# design.net
KiCad netlist of a schematic drawn in Altium Designer
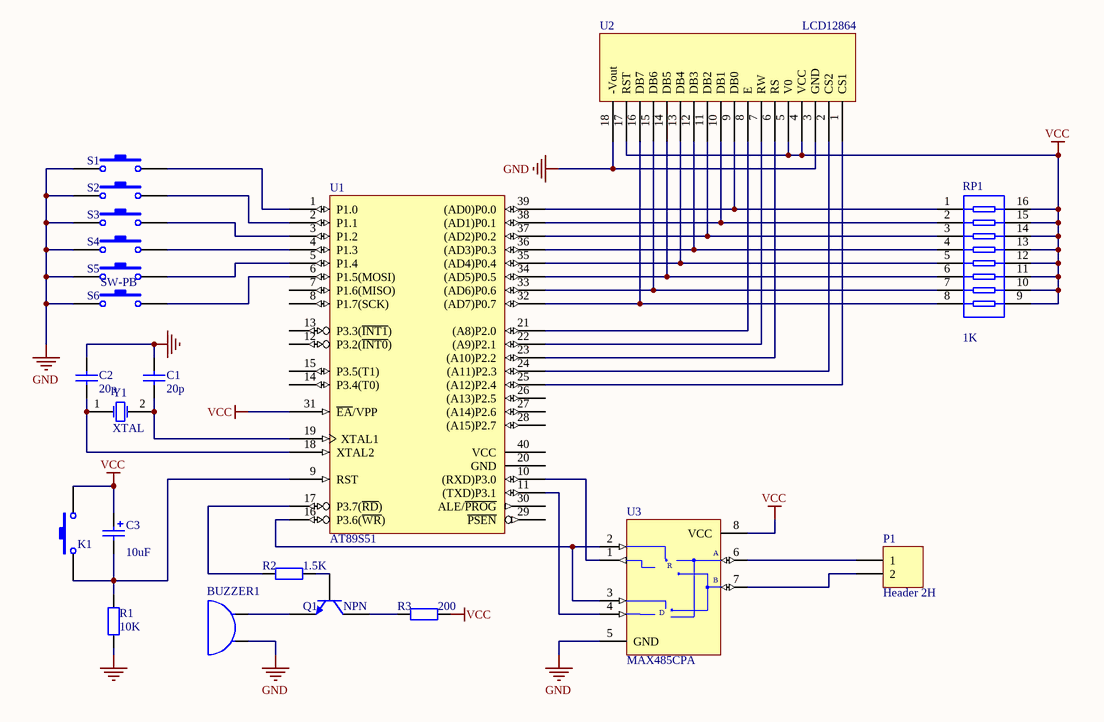
[diagram p0: 主机.SchDoc]

(export (version "E")
  (design (tool "Eeschema 10.0.6"))
  (components
    (comp (ref "BUZZER1") (value "BUZZER") (footprint "SP/10/14") (libsource (lib "原理图封装库") (part "BUZZER")))
    (comp (ref "C1")
      (value "20p")
      (footprint "RAD-0.3")
      (description "Capacitor")
      (fields (field (name "Comment") "Cap") (field (name "PUBLISHER") "Altium Limited"))
      (libsource (lib "Miscellaneous Devices") (part "Cap"))
    )
    (comp (ref "C2")
      (value "20p")
      (footprint "RAD-0.3")
      (description "Capacitor")
      (fields (field (name "Comment") "Cap") (field (name "PUBLISHER") "Altium Limited"))
      (libsource (lib "Miscellaneous Devices") (part "Cap"))
    )
    (comp (ref "C3")
      (value "10uF")
      (footprint "POLAR0.8")
      (description "Polarized Capacitor (Axial)")
      (fields (field (name "Comment") "Cap Pol2") (field (name "PUBLISHER") "Altium Limited"))
      (libsource (lib "Miscellaneous Devices") (part "Cap Pol2"))
    )
    (comp (ref "K1")
      (value "SW-PB")
      (footprint "SPST-2")
      (description "Switch")
      (fields (field (name "PUBLISHER") "Altium Limited"))
      (libsource (lib "Miscellaneous Devices") (part "SW-PB"))
    )
    (comp (ref "P1")
      (value "Header 2H")
      (footprint "HDR1X2H")
      (description "Header, 2-Pin, Right Angle")
      (fields (field (name "PUBLISHER") "Altium Limited"))
      (libsource (lib "Miscellaneous Connectors") (part "Header 2H"))
    )
    (comp (ref "Q1")
      (value "NPN")
      (footprint "TO-226")
      (description "NPN Bipolar Transistor")
      (fields (field (name "PUBLISHER") "Altium Limited"))
      (libsource (lib "Miscellaneous Devices") (part "NPN"))
    )
    (comp (ref "R1")
      (value "10K")
      (footprint "AXIAL-0.3")
      (description "Resistor")
      (fields (field (name "PUBLISHER") "Altium Limited"))
      (libsource (lib "Miscellaneous Devices") (part "Res2"))
    )
    (comp (ref "R2")
      (value "1.5K")
      (footprint "AXIAL-0.3")
      (description "Resistor")
      (fields (field (name "Comment") "10K") (field (name "PUBLISHER") "Altium Limited"))
      (libsource (lib "") (part "Res2_1"))
    )
    (comp (ref "R3")
      (value "200")
      (footprint "AXIAL-0.3")
      (description "Resistor")
      (fields (field (name "Comment") "10K") (field (name "PUBLISHER") "Altium Limited"))
      (libsource (lib "") (part "Res2_1"))
    )
    (comp (ref "RP1")
      (value "1K")
      (footprint "SSOP16")
      (description "Isolated Resistor Network")
      (fields (field (name "Comment") "Res Pack4") (field (name "PUBLISHER") "Altium Limited"))
      (libsource (lib "Miscellaneous Devices") (part "Res Pack4"))
    )
    (comp (ref "S1")
      (value "SW-PB")
      (footprint "SPST-2")
      (description "Switch")
      (fields (field (name "PUBLISHER") "Altium Limited"))
      (libsource (lib "Miscellaneous Devices") (part "SW-PB"))
    )
    (comp (ref "S2")
      (value "SW-PB")
      (footprint "SPST-2")
      (description "Switch")
      (fields (field (name "PUBLISHER") "Altium Limited"))
      (libsource (lib "Miscellaneous Devices") (part "SW-PB"))
    )
    (comp (ref "S3")
      (value "SW-PB")
      (footprint "SPST-2")
      (description "Switch")
      (fields (field (name "PUBLISHER") "Altium Limited"))
      (libsource (lib "Miscellaneous Devices") (part "SW-PB"))
    )
    (comp (ref "S4")
      (value "SW-PB")
      (footprint "SPST-2")
      (description "Switch")
      (fields (field (name "PUBLISHER") "Altium Limited"))
      (libsource (lib "Miscellaneous Devices") (part "SW-PB"))
    )
    (comp (ref "S5")
      (value "SW-PB")
      (footprint "SPST-2")
      (description "Switch")
      (fields (field (name "PUBLISHER") "Altium Limited"))
      (libsource (lib "Miscellaneous Devices") (part "SW-PB"))
    )
    (comp (ref "S6")
      (value "SW-PB")
      (footprint "SPST-2")
      (description "Switch")
      (fields (field (name "PUBLISHER") "Altium Limited"))
      (libsource (lib "Miscellaneous Devices") (part "SW-PB"))
    )
    (comp (ref "U1")
      (value "AT89S51")
      (footprint "DIP-40")
      (description "8-Bit Microcontroller with 4K ISP Flash ROM")
      (libsource (lib "Atmel Microcontroller 8051 Architecture") (part "AT89S51"))
    )
    (comp (ref "U2") (value "LCD12864") (footprint "SIL-20") (libsource (lib "LCD12864") (part "LCD12864")))
    (comp (ref "U3")
      (value "MAX485CPA")
      (footprint "PA8")
      (description "Low-Power, Slew-Rate-Limited RS-485/RS-422 Transceiver")
      (fields (field (name "PUBLISHER") "Altium Limited"))
      (libsource (lib "Maxim Communication Transceiver") (part "MAX485CPA"))
    )
    (comp (ref "Y1")
      (value "XTAL")
      (footprint "R38")
      (description "Crystal Oscillator")
      (fields (field (name "PUBLISHER") "Altium Limited"))
      (libsource (lib "Miscellaneous Devices") (part "XTAL"))
    )
  )
  (nets
    (net (code "1") (name "GND") (class "Default")
      (node (ref "BUZZER1") (pin "1") (pinfunction "1_1") (pintype "passive"))
      (node (ref "C1") (pin "1") (pinfunction "1_1") (pintype "passive"))
      (node (ref "C2") (pin "1") (pinfunction "1_1") (pintype "passive"))
      (node (ref "R1") (pin "2") (pinfunction "2_2") (pintype "passive"))
      (node (ref "S1") (pin "1") (pinfunction "1_1") (pintype "passive"))
      (node (ref "S2") (pin "1") (pinfunction "1_1") (pintype "passive"))
      (node (ref "S3") (pin "1") (pinfunction "1_1") (pintype "passive"))
      (node (ref "S4") (pin "1") (pinfunction "1_1") (pintype "passive"))
      (node (ref "S5") (pin "1") (pinfunction "1_1") (pintype "passive"))
      (node (ref "S6") (pin "1") (pinfunction "1_1") (pintype "passive"))
      (node (ref "U2") (pin "18") (pinfunction "-Vout_18") (pintype "passive"))
      (node (ref "U2") (pin "3") (pinfunction "GND_3") (pintype "passive"))
      (node (ref "U3") (pin "5") (pinfunction "GND_5") (pintype "power_in"))
    )
    (net (code "2") (name "Net-(Q1-B)") (class "Default")
      (node (ref "Q1") (pin "2") (pinfunction "B_2") (pintype "passive"))
      (node (ref "R2") (pin "2") (pinfunction "2_2") (pintype "passive"))
    )
    (net (code "3") (name "Net-(Q1-C)") (class "Default")
      (node (ref "Q1") (pin "1") (pinfunction "C_1") (pintype "passive"))
      (node (ref "R3") (pin "1") (pinfunction "1_1") (pintype "passive"))
    )
    (net (code "4") (name "Net-(Q1-E)") (class "Default")
      (node (ref "BUZZER1") (pin "2") (pinfunction "2_2") (pintype "passive"))
      (node (ref "Q1") (pin "3") (pinfunction "E_3") (pintype "passive"))
    )
    (net (code "5") (name "Net-(U1-(A8)P2.0)") (class "Default")
      (node (ref "U1") (pin "21") (pinfunction "(A8)P2.0_21") (pintype "bidirectional"))
      (node (ref "U2") (pin "8") (pinfunction "E_8") (pintype "passive"))
    )
    (net (code "6") (name "Net-(U1-(A9)P2.1)") (class "Default")
      (node (ref "U1") (pin "22") (pinfunction "(A9)P2.1_22") (pintype "bidirectional"))
      (node (ref "U2") (pin "7") (pinfunction "RW_7") (pintype "passive"))
    )
    (net (code "7") (name "Net-(U1-(A10)P2.2)") (class "Default")
      (node (ref "U1") (pin "23") (pinfunction "(A10)P2.2_23") (pintype "bidirectional"))
      (node (ref "U2") (pin "6") (pinfunction "RS_6") (pintype "passive"))
    )
    (net (code "8") (name "Net-(U1-(A11)P2.3)") (class "Default")
      (node (ref "U1") (pin "24") (pinfunction "(A11)P2.3_24") (pintype "bidirectional"))
      (node (ref "U2") (pin "2") (pinfunction "CS2_2") (pintype "passive"))
    )
    (net (code "9") (name "Net-(U1-(A12)P2.4)") (class "Default")
      (node (ref "U1") (pin "25") (pinfunction "(A12)P2.4_25") (pintype "bidirectional"))
      (node (ref "U2") (pin "1") (pinfunction "CS1_1") (pintype "passive"))
    )
    (net (code "10") (name "Net-(U1-(AD0)P0.0)") (class "Default")
      (node (ref "RP1") (pin "1") (pinfunction "1_1") (pintype "passive"))
      (node (ref "U1") (pin "39") (pinfunction "(AD0)P0.0_39") (pintype "bidirectional"))
      (node (ref "U2") (pin "9") (pinfunction "DB0_9") (pintype "passive"))
    )
    (net (code "11") (name "Net-(U1-(AD1)P0.1)") (class "Default")
      (node (ref "RP1") (pin "2") (pinfunction "2_2") (pintype "passive"))
      (node (ref "U1") (pin "38") (pinfunction "(AD1)P0.1_38") (pintype "bidirectional"))
      (node (ref "U2") (pin "10") (pinfunction "DB1_10") (pintype "passive"))
    )
    (net (code "12") (name "Net-(U1-(AD2)P0.2)") (class "Default")
      (node (ref "RP1") (pin "3") (pinfunction "3_3") (pintype "passive"))
      (node (ref "U1") (pin "37") (pinfunction "(AD2)P0.2_37") (pintype "bidirectional"))
      (node (ref "U2") (pin "11") (pinfunction "DB2_11") (pintype "passive"))
    )
    (net (code "13") (name "Net-(U1-(AD3)P0.3)") (class "Default")
      (node (ref "RP1") (pin "4") (pinfunction "4_4") (pintype "passive"))
      (node (ref "U1") (pin "36") (pinfunction "(AD3)P0.3_36") (pintype "bidirectional"))
      (node (ref "U2") (pin "12") (pinfunction "DB3_12") (pintype "passive"))
    )
    (net (code "14") (name "Net-(U1-(AD4)P0.4)") (class "Default")
      (node (ref "RP1") (pin "5") (pinfunction "5_5") (pintype "passive"))
      (node (ref "U1") (pin "35") (pinfunction "(AD4)P0.4_35") (pintype "bidirectional"))
      (node (ref "U2") (pin "13") (pinfunction "DB4_13") (pintype "passive"))
    )
    (net (code "15") (name "Net-(U1-(AD5)P0.5)") (class "Default")
      (node (ref "RP1") (pin "6") (pinfunction "6_6") (pintype "passive"))
      (node (ref "U1") (pin "34") (pinfunction "(AD5)P0.5_34") (pintype "bidirectional"))
      (node (ref "U2") (pin "14") (pinfunction "DB5_14") (pintype "passive"))
    )
    (net (code "16") (name "Net-(U1-(AD6)P0.6)") (class "Default")
      (node (ref "RP1") (pin "7") (pinfunction "7_7") (pintype "passive"))
      (node (ref "U1") (pin "33") (pinfunction "(AD6)P0.6_33") (pintype "bidirectional"))
      (node (ref "U2") (pin "15") (pinfunction "DB6_15") (pintype "passive"))
    )
    (net (code "17") (name "Net-(U1-(AD7)P0.7)") (class "Default")
      (node (ref "RP1") (pin "8") (pinfunction "8_8") (pintype "passive"))
      (node (ref "U1") (pin "32") (pinfunction "(AD7)P0.7_32") (pintype "bidirectional"))
      (node (ref "U2") (pin "16") (pinfunction "DB7_16") (pintype "passive"))
    )
    (net (code "18") (name "Net-(U1-(RXD)P3.0)") (class "Default")
      (node (ref "U1") (pin "10") (pinfunction "(RXD)P3.0_10") (pintype "bidirectional"))
      (node (ref "U3") (pin "1") (pinfunction "RO_1") (pintype "output"))
    )
    (net (code "19") (name "Net-(U1-(TXD)P3.1)") (class "Default")
      (node (ref "U1") (pin "11") (pinfunction "(TXD)P3.1_11") (pintype "bidirectional"))
      (node (ref "U3") (pin "4") (pinfunction "DI_4") (pintype "input"))
    )
    (net (code "20") (name "Net-(U1-P1.0)") (class "Default")
      (node (ref "S1") (pin "2") (pinfunction "2_2") (pintype "passive"))
      (node (ref "U1") (pin "1") (pinfunction "P1.0_1") (pintype "bidirectional"))
    )
    (net (code "21") (name "Net-(U1-P1.1)") (class "Default")
      (node (ref "S2") (pin "2") (pinfunction "2_2") (pintype "passive"))
      (node (ref "U1") (pin "2") (pinfunction "P1.1_2") (pintype "bidirectional"))
    )
    (net (code "22") (name "Net-(U1-P1.2)") (class "Default")
      (node (ref "S3") (pin "2") (pinfunction "2_2") (pintype "passive"))
      (node (ref "U1") (pin "3") (pinfunction "P1.2_3") (pintype "bidirectional"))
    )
    (net (code "23") (name "Net-(U1-P1.3)") (class "Default")
      (node (ref "S4") (pin "2") (pinfunction "2_2") (pintype "passive"))
      (node (ref "U1") (pin "4") (pinfunction "P1.3_4") (pintype "bidirectional"))
    )
    (net (code "24") (name "Net-(U1-P1.4)") (class "Default")
      (node (ref "S5") (pin "2") (pinfunction "2_2") (pintype "passive"))
      (node (ref "U1") (pin "5") (pinfunction "P1.4_5") (pintype "bidirectional"))
    )
    (net (code "25") (name "Net-(U1-P1.5(MOSI))") (class "Default")
      (node (ref "S6") (pin "2") (pinfunction "2_2") (pintype "passive"))
      (node (ref "U1") (pin "6") (pinfunction "P1.5(MOSI)_6") (pintype "bidirectional"))
    )
    (net (code "26") (name "Net-(U1-P3.6(~{WR}))") (class "Default")
      (node (ref "U1") (pin "16") (pinfunction "P3.6(~{WR})_16") (pintype "bidirectional"))
      (node (ref "U3") (pin "2") (pinfunction "~{RE}_2") (pintype "input"))
      (node (ref "U3") (pin "3") (pinfunction "DE_3") (pintype "input"))
    )
    (net (code "27") (name "Net-(U1-P3.7(~{RD}))") (class "Default")
      (node (ref "R2") (pin "1") (pinfunction "1_1") (pintype "passive"))
      (node (ref "U1") (pin "17") (pinfunction "P3.7(~{RD})_17") (pintype "bidirectional"))
    )
    (net (code "28") (name "Net-(U1-RST)") (class "Default")
      (node (ref "C3") (pin "2") (pinfunction "2_2") (pintype "passive"))
      (node (ref "K1") (pin "1") (pinfunction "1_1") (pintype "passive"))
      (node (ref "R1") (pin "1") (pinfunction "1_1") (pintype "passive"))
      (node (ref "U1") (pin "9") (pinfunction "RST_9") (pintype "input"))
    )
    (net (code "29") (name "Net-(U1-XTAL1)") (class "Default")
      (node (ref "C1") (pin "2") (pinfunction "2_2") (pintype "passive"))
      (node (ref "U1") (pin "19") (pinfunction "XTAL1_19") (pintype "input"))
      (node (ref "Y1") (pin "2") (pinfunction "OSC2_2") (pintype "passive"))
    )
    (net (code "30") (name "Net-(U1-XTAL2)") (class "Default")
      (node (ref "C2") (pin "2") (pinfunction "2_2") (pintype "passive"))
      (node (ref "U1") (pin "18") (pinfunction "XTAL2_18") (pintype "input"))
      (node (ref "Y1") (pin "1") (pinfunction "OSC1_1") (pintype "passive"))
    )
    (net (code "31") (name "Net-(U3-A)") (class "Default")
      (node (ref "P1") (pin "1") (pinfunction "1_1") (pintype "passive"))
      (node (ref "U3") (pin "6") (pinfunction "A_6") (pintype "bidirectional"))
    )
    (net (code "32") (name "Net-(U3-B)") (class "Default")
      (node (ref "P1") (pin "2") (pinfunction "2_2") (pintype "passive"))
      (node (ref "U3") (pin "7") (pinfunction "B_7") (pintype "bidirectional"))
    )
    (net (code "33") (name "VCC") (class "Default")
      (node (ref "C3") (pin "1") (pinfunction "1_1") (pintype "passive"))
      (node (ref "K1") (pin "2") (pinfunction "2_2") (pintype "passive"))
      (node (ref "R3") (pin "2") (pinfunction "2_2") (pintype "passive"))
      (node (ref "RP1") (pin "10") (pinfunction "10_10") (pintype "passive"))
      (node (ref "RP1") (pin "11") (pinfunction "11_11") (pintype "passive"))
      (node (ref "RP1") (pin "12") (pinfunction "12_12") (pintype "passive"))
      (node (ref "RP1") (pin "13") (pinfunction "13_13") (pintype "passive"))
      (node (ref "RP1") (pin "14") (pinfunction "14_14") (pintype "passive"))
      (node (ref "RP1") (pin "15") (pinfunction "15_15") (pintype "passive"))
      (node (ref "RP1") (pin "16") (pinfunction "16_16") (pintype "passive"))
      (node (ref "RP1") (pin "9") (pinfunction "9_9") (pintype "passive"))
      (node (ref "U1") (pin "31") (pinfunction "~{EA}/VPP_31") (pintype "input"))
      (node (ref "U2") (pin "17") (pinfunction "RST_17") (pintype "passive"))
      (node (ref "U2") (pin "4") (pinfunction "VCC_4") (pintype "passive"))
      (node (ref "U2") (pin "5") (pinfunction "V0_5") (pintype "passive"))
      (node (ref "U3") (pin "8") (pinfunction "VCC_8") (pintype "power_in"))
    )
    (net (code "34") (name "unconnected-(U1-(A13)P2.5-Pad26)") (class "Default")
      (node (ref "U1") (pin "26") (pinfunction "(A13)P2.5_26") (pintype "bidirectional"))
    )
    (net (code "35") (name "unconnected-(U1-(A14)P2.6-Pad27)") (class "Default")
      (node (ref "U1") (pin "27") (pinfunction "(A14)P2.6_27") (pintype "bidirectional"))
    )
    (net (code "36") (name "unconnected-(U1-(A15)P2.7-Pad28)") (class "Default")
      (node (ref "U1") (pin "28") (pinfunction "(A15)P2.7_28") (pintype "bidirectional"))
    )
    (net (code "37") (name "unconnected-(U1-ALE{slash}~{PROG}-Pad30)") (class "Default")
      (node (ref "U1") (pin "30") (pinfunction "ALE/~{PROG}_30") (pintype "output"))
    )
    (net (code "38") (name "unconnected-(U1-GND-Pad20)") (class "Default")
      (node (ref "U1") (pin "20") (pinfunction "GND_20") (pintype "power_in"))
    )
    (net (code "39") (name "unconnected-(U1-P1.6(MISO)-Pad7)") (class "Default")
      (node (ref "U1") (pin "7") (pinfunction "P1.6(MISO)_7") (pintype "bidirectional"))
    )
    (net (code "40") (name "unconnected-(U1-P1.7(SCK)-Pad8)") (class "Default")
      (node (ref "U1") (pin "8") (pinfunction "P1.7(SCK)_8") (pintype "bidirectional"))
    )
    (net (code "41") (name "unconnected-(U1-P3.2(~{INT0})-Pad12)") (class "Default")
      (node (ref "U1") (pin "12") (pinfunction "P3.2(~{INT0})_12") (pintype "bidirectional"))
    )
    (net (code "42") (name "unconnected-(U1-P3.3(~{INT1})-Pad13)") (class "Default")
      (node (ref "U1") (pin "13") (pinfunction "P3.3(~{INT1})_13") (pintype "bidirectional"))
    )
    (net (code "43") (name "unconnected-(U1-P3.4(T0)-Pad14)") (class "Default")
      (node (ref "U1") (pin "14") (pinfunction "P3.4(T0)_14") (pintype "bidirectional"))
    )
    (net (code "44") (name "unconnected-(U1-P3.5(T1)-Pad15)") (class "Default")
      (node (ref "U1") (pin "15") (pinfunction "P3.5(T1)_15") (pintype "bidirectional"))
    )
    (net (code "45") (name "unconnected-(U1-VCC-Pad40)") (class "Default")
      (node (ref "U1") (pin "40") (pinfunction "VCC_40") (pintype "power_in"))
    )
    (net (code "46") (name "unconnected-(U1-~{PSEN}-Pad29)") (class "Default")
      (node (ref "U1") (pin "29") (pinfunction "~{PSEN}_29") (pintype "output"))
    )
  )
)
